# BuoyLoRaNode_Schematic.net
KiCad netlist of a schematic drawn in Altium Designer
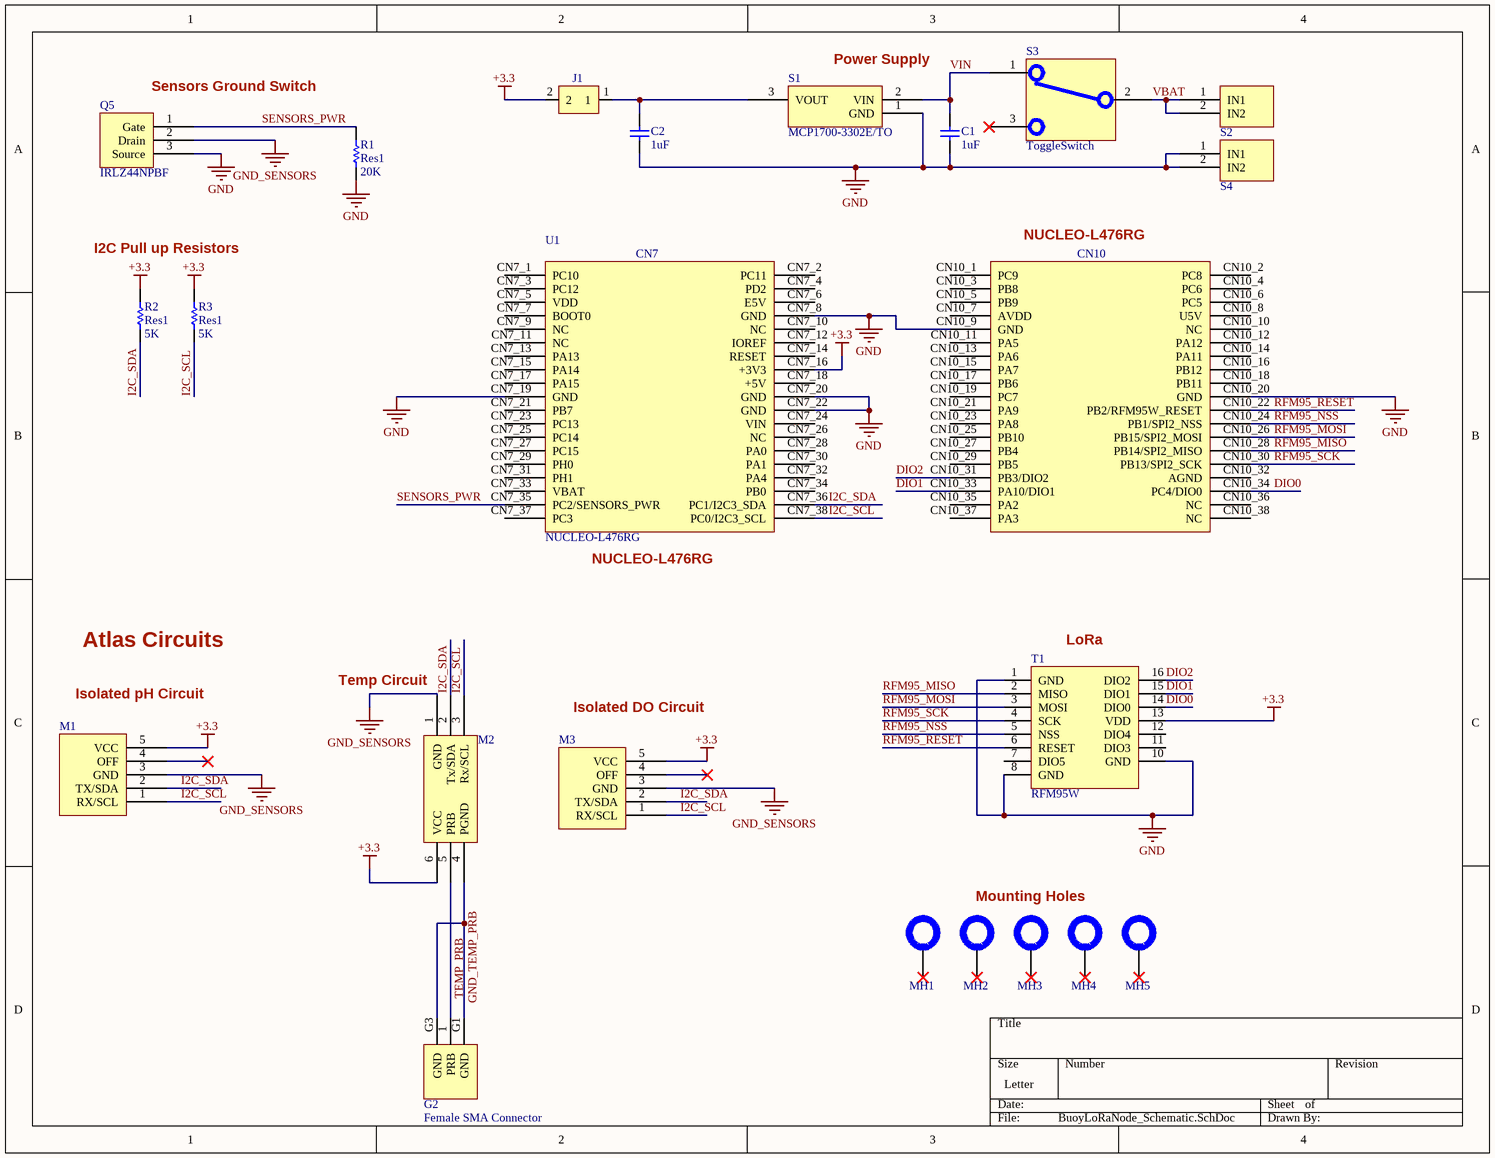
[diagram p0: BuoyLoRaNode_Schematic.SchDoc]

(export (version "E")
  (design (tool "Eeschema 10.0.6"))
  (components
    (comp (ref "C1")
      (value "1uF")
      (footprint "C1uFTantalum")
      (description "CAP TANT 1UF 10% 35V RADIAL")
      (fields
        (field (name "MANUFACTURER") "KEMET")
        (field (name "MANUFACTURER PART NUMBER") "T350A105K035AS7301")
      )
      (libsource (lib "BuoyLoRaNode") (part "T350A105K035AS7301"))
    )
    (comp (ref "C2")
      (value "1uF")
      (footprint "C1uFTantalum")
      (description "CAP TANT 1UF 10% 35V RADIAL")
      (fields
        (field (name "MANUFACTURER") "KEMET")
        (field (name "MANUFACTURER PART NUMBER") "T350A105K035AS7301")
      )
      (libsource (lib "BuoyLoRaNode") (part "T350A105K035AS7301"))
    )
    (comp (ref "G2")
      (value "Female SMA Connector")
      (footprint "SmaFemaleConnectorEdgeMount")
      (libsource (lib "BuoyLoRaNode") (part "Female SMA Connector"))
    )
    (comp (ref "J1")
      (value "2PinMaleJumper")
      (footprint "2MaleJumper")
      (libsource (lib "BuoyLoRaNode") (part "2PinMaleJumper"))
    )
    (comp (ref "M1")
      (value "Isolated pH Sensor")
      (footprint "ATLASISOLATEDPHSENSOR")
      (libsource (lib "BuoyLoRaNode") (part "Atlas Isolated pH Sensor"))
    )
    (comp (ref "M2")
      (value "EZO™ RTD Temperature Circuit")
      (footprint "AtlasTemperatureSensor")
      (libsource (lib "BuoyLoRaNode") (part "EZO™ RTD Temperature Circuit"))
    )
    (comp (ref "M3")
      (value "Isolated DO Sensor")
      (footprint "ATLASISOLATEDDOSENSOR")
      (libsource (lib "BuoyLoRaNode") (part "Atlas Isolated DO Sensor"))
    )
    (comp (ref "MH1")
      (value "MountingHole_3.4mmHole")
      (footprint "MountingHole")
      (libsource (lib "BuoyLoRaNode") (part "MountingHole"))
    )
    (comp (ref "MH2")
      (value "MountingHole_3.4mmHole")
      (footprint "MountingHole")
      (libsource (lib "BuoyLoRaNode") (part "MountingHole"))
    )
    (comp (ref "MH3")
      (value "MountingHole_3.4mmHole")
      (footprint "MountingHole")
      (libsource (lib "BuoyLoRaNode") (part "MountingHole"))
    )
    (comp (ref "MH4")
      (value "MountingHole_3.4mmHole")
      (footprint "MountingHole")
      (libsource (lib "BuoyLoRaNode") (part "MountingHole"))
    )
    (comp (ref "MH5")
      (value "MountingHole_3.4mmHole")
      (footprint "MountingHole")
      (libsource (lib "BuoyLoRaNode") (part "MountingHole"))
    )
    (comp (ref "Q5")
      (value "IRLZ44NPBF")
      (footprint "IRLZ44N")
      (description "INFINEON - IRLZ44NPBF - MOSFET, N, 55V, 41A, TO-220")
      (fields (field (name "MANUFACTURER") "International Rectifier"))
      (libsource (lib "BuoyLoRaNode") (part "IRLZ44NPBF"))
    )
    (comp (ref "R1")
      (value "Res1")
      (footprint "AXIAL-0.3")
      (description "Resistor")
      (fields (field (name "ALTIUM_VALUE") "20K") (field (name "PUBLISHER") "Altium Limited"))
      (libsource (lib "Miscellaneous Devices") (part "Res1"))
    )
    (comp (ref "R2")
      (value "Res1")
      (footprint "AXIAL-0.3")
      (description "Resistor")
      (fields (field (name "ALTIUM_VALUE") "5K") (field (name "PUBLISHER") "Altium Limited"))
      (libsource (lib "Miscellaneous Devices") (part "Res1"))
    )
    (comp (ref "R3")
      (value "Res1")
      (footprint "AXIAL-0.3")
      (description "Resistor")
      (fields (field (name "ALTIUM_VALUE") "5K") (field (name "PUBLISHER") "Altium Limited"))
      (libsource (lib "Miscellaneous Devices") (part "Res1"))
    )
    (comp (ref "S1")
      (value "MCP1700-3302E/TO")
      (footprint "MCP1700")
      (description "LDO Regulator Pos 3.3V 0.25A 3-Pin TO-92 Bag")
      (fields (field (name "MANUFACTURER") "Microchip"))
      (libsource (lib "GPSLoRaNode") (part "MCP1700-3302E/TO"))
    )
    (comp (ref "S2")
      (value "2PositionScrewTerminal")
      (footprint "2POSITIONSCREWTERMINAL")
      (fields
        (field (name "MANUFACTURER") "Phoenix Contact")
        (field (name "MANUFACTURER PART NUMBER") "1725656")
        (field (name "VOLTAGE") "125V")
      )
      (libsource (lib "BuoyLoRaNode") (part "2PositionScrewTerminal"))
    )
    (comp (ref "S3")
      (value "ToggleSwitch")
      (footprint "ToggleSwitch")
      (libsource (lib "BuoyLoRaNode") (part "ToggleSwitch"))
    )
    (comp (ref "S4")
      (value "2PositionScrewTerminal")
      (footprint "2POSITIONSCREWTERMINAL")
      (fields
        (field (name "MANUFACTURER") "Phoenix Contact")
        (field (name "MANUFACTURER PART NUMBER") "1725656")
        (field (name "VOLTAGE") "125V")
      )
      (libsource (lib "BuoyLoRaNode") (part "2PositionScrewTerminal"))
    )
    (comp (ref "T1")
      (value "RFM95W")
      (footprint "RFM95WBreakout")
      (description "RFM95W Breakout Board")
      (fields (field (name "MANUFACTURER") "Molex") (field (name "MANUFACTURER PART NUMBER") "22-10-2061"))
      (libsource (lib "BuoyLoRaNode") (part "RFM95W"))
    )
    (comp (ref "U1")
      (value "NUCLEO-L476RG")
      (footprint "NUCLEOL476RG")
      (description "16/32-BITS MICROS")
      (fields (field (name "MANUFACTURER") "STMicroelectronics"))
      (libsource (lib "BuoyLoRaNode") (part "NUCLEO-L476RG"))
    )
  )
  (nets
    (net (code "1") (name "+3.3") (class "Default")
      (node (ref "J1") (pin "2") (pinfunction "2_2") (pintype "passive"))
      (node (ref "M1") (pin "5") (pinfunction "VCC_5") (pintype "passive"))
      (node (ref "M2") (pin "6") (pinfunction "VCC_6") (pintype "passive"))
      (node (ref "M3") (pin "5") (pinfunction "VCC_5") (pintype "passive"))
      (node (ref "R2") (pin "2") (pinfunction "2_2") (pintype "passive"))
      (node (ref "R3") (pin "2") (pinfunction "2_2") (pintype "passive"))
      (node (ref "T1") (pin "13") (pinfunction "VDD_13") (pintype "passive"))
      (node (ref "U1") (pin "CN7_16") (pinfunction "+3V3_CN7_16") (pintype "passive"))
    )
    (net (code "2") (name "/DIO0") (class "Default")
      (node (ref "T1") (pin "14") (pinfunction "DIO0_14") (pintype "passive"))
      (node (ref "U1") (pin "CN10_34") (pinfunction "PC4/DIO0_CN10_34") (pintype "passive"))
    )
    (net (code "3") (name "/DIO1") (class "Default")
      (node (ref "T1") (pin "15") (pinfunction "DIO1_15") (pintype "passive"))
      (node (ref "U1") (pin "CN10_33") (pinfunction "PA10/DIO1_CN10_33") (pintype "passive"))
    )
    (net (code "4") (name "/DIO2") (class "Default")
      (node (ref "T1") (pin "16") (pinfunction "DIO2_16") (pintype "passive"))
      (node (ref "U1") (pin "CN10_31") (pinfunction "PB3/DIO2_CN10_31") (pintype "passive"))
    )
    (net (code "5") (name "/GND_TEMP_PRB") (class "Default")
      (node (ref "G2") (pin "G1") (pinfunction "GND_G1") (pintype "passive"))
      (node (ref "G2") (pin "G3") (pinfunction "GND_G3") (pintype "passive"))
      (node (ref "M2") (pin "4") (pinfunction "PGND_4") (pintype "passive"))
    )
    (net (code "6") (name "/I2C_SCL") (class "Default")
      (node (ref "M1") (pin "1") (pinfunction "RX/SCL_1") (pintype "passive"))
      (node (ref "M2") (pin "3") (pinfunction "Rx/SCL_3") (pintype "passive"))
      (node (ref "M3") (pin "1") (pinfunction "RX/SCL_1") (pintype "passive"))
      (node (ref "R3") (pin "1") (pinfunction "1_1") (pintype "passive"))
      (node (ref "U1") (pin "CN7_38") (pinfunction "PC0/I2C3_SCL_CN7_38") (pintype "passive"))
    )
    (net (code "7") (name "/I2C_SDA") (class "Default")
      (node (ref "M1") (pin "2") (pinfunction "TX/SDA_2") (pintype "passive"))
      (node (ref "M2") (pin "2") (pinfunction "Tx/SDA_2") (pintype "passive"))
      (node (ref "M3") (pin "2") (pinfunction "TX/SDA_2") (pintype "passive"))
      (node (ref "R2") (pin "1") (pinfunction "1_1") (pintype "passive"))
      (node (ref "U1") (pin "CN7_36") (pinfunction "PC1/I2C3_SDA_CN7_36") (pintype "passive"))
    )
    (net (code "8") (name "/RFM95_MISO") (class "Default")
      (node (ref "T1") (pin "2") (pinfunction "MISO_2") (pintype "passive"))
      (node (ref "U1") (pin "CN10_28") (pinfunction "PB14/SPI2_MISO_CN10_28") (pintype "passive"))
    )
    (net (code "9") (name "/RFM95_MOSI") (class "Default")
      (node (ref "T1") (pin "3") (pinfunction "MOSI_3") (pintype "passive"))
      (node (ref "U1") (pin "CN10_26") (pinfunction "PB15/SPI2_MOSI_CN10_26") (pintype "passive"))
    )
    (net (code "10") (name "/RFM95_NSS") (class "Default")
      (node (ref "T1") (pin "5") (pinfunction "NSS_5") (pintype "passive"))
      (node (ref "U1") (pin "CN10_24") (pinfunction "PB1/SPI2_NSS_CN10_24") (pintype "passive"))
    )
    (net (code "11") (name "/RFM95_RESET") (class "Default")
      (node (ref "T1") (pin "6") (pinfunction "RESET_6") (pintype "passive"))
      (node (ref "U1") (pin "CN10_22") (pinfunction "PB2/RFM95W_RESET_CN10_22") (pintype "passive"))
    )
    (net (code "12") (name "/RFM95_SCK") (class "Default")
      (node (ref "T1") (pin "4") (pinfunction "SCK_4") (pintype "passive"))
      (node (ref "U1") (pin "CN10_30") (pinfunction "PB13/SPI2_SCK_CN10_30") (pintype "passive"))
    )
    (net (code "13") (name "/SENSORS_PWR") (class "Default")
      (node (ref "Q5") (pin "1") (pinfunction "Gate_1") (pintype "passive"))
      (node (ref "R1") (pin "2") (pinfunction "2_2") (pintype "passive"))
      (node (ref "U1") (pin "CN7_35") (pinfunction "PC2/SENSORS_PWR_CN7_35") (pintype "passive"))
    )
    (net (code "14") (name "/TEMP_PRB") (class "Default")
      (node (ref "G2") (pin "1") (pinfunction "PRB_1") (pintype "passive"))
      (node (ref "M2") (pin "5") (pinfunction "PRB_5") (pintype "passive"))
    )
    (net (code "15") (name "/VBAT") (class "Default")
      (node (ref "S2") (pin "1") (pinfunction "IN1_1") (pintype "passive"))
      (node (ref "S2") (pin "2") (pinfunction "IN2_2") (pintype "passive"))
      (node (ref "S3") (pin "2") (pinfunction "COM_2") (pintype "passive"))
    )
    (net (code "16") (name "/VIN") (class "Default")
      (node (ref "C1") (pin "2") (pinfunction "2_2") (pintype "passive"))
      (node (ref "S1") (pin "2") (pinfunction "VIN_2") (pintype "passive"))
      (node (ref "S3") (pin "1") (pinfunction "L1_1") (pintype "passive"))
    )
    (net (code "17") (name "GND") (class "Default")
      (node (ref "C1") (pin "1") (pinfunction "1_1") (pintype "passive"))
      (node (ref "C2") (pin "1") (pinfunction "1_1") (pintype "passive"))
      (node (ref "Q5") (pin "3") (pinfunction "Source_3") (pintype "passive"))
      (node (ref "R1") (pin "1") (pinfunction "1_1") (pintype "passive"))
      (node (ref "S1") (pin "1") (pinfunction "GND_1") (pintype "passive"))
      (node (ref "S4") (pin "1") (pinfunction "IN1_1") (pintype "passive"))
      (node (ref "S4") (pin "2") (pinfunction "IN2_2") (pintype "passive"))
      (node (ref "T1") (pin "1") (pinfunction "GND_1") (pintype "passive"))
      (node (ref "T1") (pin "10") (pinfunction "GND_10") (pintype "passive"))
      (node (ref "T1") (pin "8") (pinfunction "GND_8") (pintype "passive"))
      (node (ref "U1") (pin "CN10_20") (pinfunction "GND_CN10_20") (pintype "passive"))
      (node (ref "U1") (pin "CN10_9") (pinfunction "GND_CN10_9") (pintype "passive"))
      (node (ref "U1") (pin "CN7_19") (pinfunction "GND_CN7_19") (pintype "passive"))
      (node (ref "U1") (pin "CN7_20") (pinfunction "GND_CN7_20") (pintype "passive"))
      (node (ref "U1") (pin "CN7_22") (pinfunction "GND_CN7_22") (pintype "passive"))
      (node (ref "U1") (pin "CN7_8") (pinfunction "GND_CN7_8") (pintype "passive"))
    )
    (net (code "18") (name "GND_SENSORS") (class "Default")
      (node (ref "M1") (pin "3") (pinfunction "GND_3") (pintype "passive"))
      (node (ref "M2") (pin "1") (pinfunction "GND_1") (pintype "passive"))
      (node (ref "M3") (pin "3") (pinfunction "GND_3") (pintype "passive"))
      (node (ref "Q5") (pin "2") (pinfunction "Drain_2") (pintype "passive"))
    )
    (net (code "19") (name "Net-(S1-VOUT)") (class "Default")
      (node (ref "C2") (pin "2") (pinfunction "2_2") (pintype "passive"))
      (node (ref "J1") (pin "1") (pinfunction "1_1") (pintype "passive"))
      (node (ref "S1") (pin "3") (pinfunction "VOUT_3") (pintype "passive"))
    )
    (net (code "20") (name "unconnected-(M1-OFF-Pad4)") (class "Default")
      (node (ref "M1") (pin "4") (pinfunction "OFF_4") (pintype "passive+no_connect"))
    )
    (net (code "21") (name "unconnected-(M3-OFF-Pad4)") (class "Default")
      (node (ref "M3") (pin "4") (pinfunction "OFF_4") (pintype "passive+no_connect"))
    )
    (net (code "22") (name "unconnected-(MH1-Pad1)") (class "Default")
      (node (ref "MH1") (pin "1") (pinfunction "1_1") (pintype "passive+no_connect"))
    )
    (net (code "23") (name "unconnected-(MH2-Pad1)") (class "Default")
      (node (ref "MH2") (pin "1") (pinfunction "1_1") (pintype "passive+no_connect"))
    )
    (net (code "24") (name "unconnected-(MH3-Pad1)") (class "Default")
      (node (ref "MH3") (pin "1") (pinfunction "1_1") (pintype "passive+no_connect"))
    )
    (net (code "25") (name "unconnected-(MH4-Pad1)") (class "Default")
      (node (ref "MH4") (pin "1") (pinfunction "1_1") (pintype "passive+no_connect"))
    )
    (net (code "26") (name "unconnected-(MH5-Pad1)") (class "Default")
      (node (ref "MH5") (pin "1") (pinfunction "1_1") (pintype "passive+no_connect"))
    )
    (net (code "27") (name "unconnected-(S3-L2-Pad3)") (class "Default")
      (node (ref "S3") (pin "3") (pinfunction "L2_3") (pintype "passive+no_connect"))
    )
    (net (code "28") (name "unconnected-(T1-DIO3-Pad11)") (class "Default")
      (node (ref "T1") (pin "11") (pinfunction "DIO3_11") (pintype "passive"))
    )
    (net (code "29") (name "unconnected-(T1-DIO4-Pad12)") (class "Default")
      (node (ref "T1") (pin "12") (pinfunction "DIO4_12") (pintype "passive"))
    )
    (net (code "30") (name "unconnected-(T1-DIO5-Pad7)") (class "Default")
      (node (ref "T1") (pin "7") (pinfunction "DIO5_7") (pintype "passive"))
    )
    (net (code "31") (name "unconnected-(U1-+5V-PadCN7_18)") (class "Default")
      (node (ref "U1") (pin "CN7_18") (pinfunction "+5V_CN7_18") (pintype "passive"))
    )
    (net (code "32") (name "unconnected-(U1-AGND-PadCN10_32)") (class "Default")
      (node (ref "U1") (pin "CN10_32") (pinfunction "AGND_CN10_32") (pintype "passive"))
    )
    (net (code "33") (name "unconnected-(U1-AVDD-PadCN10_7)") (class "Default")
      (node (ref "U1") (pin "CN10_7") (pinfunction "AVDD_CN10_7") (pintype "passive"))
    )
    (net (code "34") (name "unconnected-(U1-BOOT0-PadCN7_7)") (class "Default")
      (node (ref "U1") (pin "CN7_7") (pinfunction "BOOT0_CN7_7") (pintype "passive"))
    )
    (net (code "35") (name "unconnected-(U1-E5V-PadCN7_6)") (class "Default")
      (node (ref "U1") (pin "CN7_6") (pinfunction "E5V_CN7_6") (pintype "passive"))
    )
    (net (code "36") (name "unconnected-(U1-IOREF-PadCN7_12)") (class "Default")
      (node (ref "U1") (pin "CN7_12") (pinfunction "IOREF_CN7_12") (pintype "passive"))
    )
    (net (code "37") (name "unconnected-(U1-NC-PadCN7_9)") (class "Default")
      (node (ref "U1") (pin "CN7_9") (pinfunction "NC_CN7_9") (pintype "passive"))
    )
    (net (code "38") (name "unconnected-(U1-NC-PadCN7_10)") (class "Default")
      (node (ref "U1") (pin "CN7_10") (pinfunction "NC_CN7_10") (pintype "passive"))
    )
    (net (code "39") (name "unconnected-(U1-NC-PadCN7_11)") (class "Default")
      (node (ref "U1") (pin "CN7_11") (pinfunction "NC_CN7_11") (pintype "passive"))
    )
    (net (code "40") (name "unconnected-(U1-NC-PadCN7_26)") (class "Default")
      (node (ref "U1") (pin "CN7_26") (pinfunction "NC_CN7_26") (pintype "passive"))
    )
    (net (code "41") (name "unconnected-(U1-NC-PadCN10_10)") (class "Default")
      (node (ref "U1") (pin "CN10_10") (pinfunction "NC_CN10_10") (pintype "passive"))
    )
    (net (code "42") (name "unconnected-(U1-NC-PadCN10_36)") (class "Default")
      (node (ref "U1") (pin "CN10_36") (pinfunction "NC_CN10_36") (pintype "passive"))
    )
    (net (code "43") (name "unconnected-(U1-NC-PadCN10_38)") (class "Default")
      (node (ref "U1") (pin "CN10_38") (pinfunction "NC_CN10_38") (pintype "passive"))
    )
    (net (code "44") (name "unconnected-(U1-PA0-PadCN7_28)") (class "Default")
      (node (ref "U1") (pin "CN7_28") (pinfunction "PA0_CN7_28") (pintype "passive"))
    )
    (net (code "45") (name "unconnected-(U1-PA1-PadCN7_30)") (class "Default")
      (node (ref "U1") (pin "CN7_30") (pinfunction "PA1_CN7_30") (pintype "passive"))
    )
    (net (code "46") (name "unconnected-(U1-PA2-PadCN10_35)") (class "Default")
      (node (ref "U1") (pin "CN10_35") (pinfunction "PA2_CN10_35") (pintype "passive"))
    )
    (net (code "47") (name "unconnected-(U1-PA3-PadCN10_37)") (class "Default")
      (node (ref "U1") (pin "CN10_37") (pinfunction "PA3_CN10_37") (pintype "passive"))
    )
    (net (code "48") (name "unconnected-(U1-PA4-PadCN7_32)") (class "Default")
      (node (ref "U1") (pin "CN7_32") (pinfunction "PA4_CN7_32") (pintype "passive"))
    )
    (net (code "49") (name "unconnected-(U1-PA5-PadCN10_11)") (class "Default")
      (node (ref "U1") (pin "CN10_11") (pinfunction "PA5_CN10_11") (pintype "passive"))
    )
    (net (code "50") (name "unconnected-(U1-PA6-PadCN10_13)") (class "Default")
      (node (ref "U1") (pin "CN10_13") (pinfunction "PA6_CN10_13") (pintype "passive"))
    )
    (net (code "51") (name "unconnected-(U1-PA7-PadCN10_15)") (class "Default")
      (node (ref "U1") (pin "CN10_15") (pinfunction "PA7_CN10_15") (pintype "passive"))
    )
    (net (code "52") (name "unconnected-(U1-PA8-PadCN10_23)") (class "Default")
      (node (ref "U1") (pin "CN10_23") (pinfunction "PA8_CN10_23") (pintype "passive"))
    )
    (net (code "53") (name "unconnected-(U1-PA9-PadCN10_21)") (class "Default")
      (node (ref "U1") (pin "CN10_21") (pinfunction "PA9_CN10_21") (pintype "passive"))
    )
    (net (code "54") (name "unconnected-(U1-PA11-PadCN10_14)") (class "Default")
      (node (ref "U1") (pin "CN10_14") (pinfunction "PA11_CN10_14") (pintype "passive"))
    )
    (net (code "55") (name "unconnected-(U1-PA12-PadCN10_12)") (class "Default")
      (node (ref "U1") (pin "CN10_12") (pinfunction "PA12_CN10_12") (pintype "passive"))
    )
    (net (code "56") (name "unconnected-(U1-PA13-PadCN7_13)") (class "Default")
      (node (ref "U1") (pin "CN7_13") (pinfunction "PA13_CN7_13") (pintype "passive"))
    )
    (net (code "57") (name "unconnected-(U1-PA14-PadCN7_15)") (class "Default")
      (node (ref "U1") (pin "CN7_15") (pinfunction "PA14_CN7_15") (pintype "passive"))
    )
    (net (code "58") (name "unconnected-(U1-PA15-PadCN7_17)") (class "Default")
      (node (ref "U1") (pin "CN7_17") (pinfunction "PA15_CN7_17") (pintype "passive"))
    )
    (net (code "59") (name "unconnected-(U1-PB0-PadCN7_34)") (class "Default")
      (node (ref "U1") (pin "CN7_34") (pinfunction "PB0_CN7_34") (pintype "passive"))
    )
    (net (code "60") (name "unconnected-(U1-PB4-PadCN10_27)") (class "Default")
      (node (ref "U1") (pin "CN10_27") (pinfunction "PB4_CN10_27") (pintype "passive"))
    )
    (net (code "61") (name "unconnected-(U1-PB5-PadCN10_29)") (class "Default")
      (node (ref "U1") (pin "CN10_29") (pinfunction "PB5_CN10_29") (pintype "passive"))
    )
    (net (code "62") (name "unconnected-(U1-PB6-PadCN10_17)") (class "Default")
      (node (ref "U1") (pin "CN10_17") (pinfunction "PB6_CN10_17") (pintype "passive"))
    )
    (net (code "63") (name "unconnected-(U1-PB7-PadCN7_21)") (class "Default")
      (node (ref "U1") (pin "CN7_21") (pinfunction "PB7_CN7_21") (pintype "passive"))
    )
    (net (code "64") (name "unconnected-(U1-PB8-PadCN10_3)") (class "Default")
      (node (ref "U1") (pin "CN10_3") (pinfunction "PB8_CN10_3") (pintype "passive"))
    )
    (net (code "65") (name "unconnected-(U1-PB9-PadCN10_5)") (class "Default")
      (node (ref "U1") (pin "CN10_5") (pinfunction "PB9_CN10_5") (pintype "passive"))
    )
    (net (code "66") (name "unconnected-(U1-PB10-PadCN10_25)") (class "Default")
      (node (ref "U1") (pin "CN10_25") (pinfunction "PB10_CN10_25") (pintype "passive"))
    )
    (net (code "67") (name "unconnected-(U1-PB11-PadCN10_18)") (class "Default")
      (node (ref "U1") (pin "CN10_18") (pinfunction "PB11_CN10_18") (pintype "passive"))
    )
    (net (code "68") (name "unconnected-(U1-PB12-PadCN10_16)") (class "Default")
      (node (ref "U1") (pin "CN10_16") (pinfunction "PB12_CN10_16") (pintype "passive"))
    )
    (net (code "69") (name "unconnected-(U1-PC3-PadCN7_37)") (class "Default")
      (node (ref "U1") (pin "CN7_37") (pinfunction "PC3_CN7_37") (pintype "passive"))
    )
    (net (code "70") (name "unconnected-(U1-PC5-PadCN10_6)") (class "Default")
      (node (ref "U1") (pin "CN10_6") (pinfunction "PC5_CN10_6") (pintype "passive"))
    )
    (net (code "71") (name "unconnected-(U1-PC6-PadCN10_4)") (class "Default")
      (node (ref "U1") (pin "CN10_4") (pinfunction "PC6_CN10_4") (pintype "passive"))
    )
    (net (code "72") (name "unconnected-(U1-PC7-PadCN10_19)") (class "Default")
      (node (ref "U1") (pin "CN10_19") (pinfunction "PC7_CN10_19") (pintype "passive"))
    )
    (net (code "73") (name "unconnected-(U1-PC8-PadCN10_2)") (class "Default")
      (node (ref "U1") (pin "CN10_2") (pinfunction "PC8_CN10_2") (pintype "passive"))
    )
    (net (code "74") (name "unconnected-(U1-PC9-PadCN10_1)") (class "Default")
      (node (ref "U1") (pin "CN10_1") (pinfunction "PC9_CN10_1") (pintype "passive"))
    )
    (net (code "75") (name "unconnected-(U1-PC10-PadCN7_1)") (class "Default")
      (node (ref "U1") (pin "CN7_1") (pinfunction "PC10_CN7_1") (pintype "passive"))
    )
    (net (code "76") (name "unconnected-(U1-PC11-PadCN7_2)") (class "Default")
      (node (ref "U1") (pin "CN7_2") (pinfunction "PC11_CN7_2") (pintype "passive"))
    )
    (net (code "77") (name "unconnected-(U1-PC12-PadCN7_3)") (class "Default")
      (node (ref "U1") (pin "CN7_3") (pinfunction "PC12_CN7_3") (pintype "passive"))
    )
    (net (code "78") (name "unconnected-(U1-PC13-PadCN7_23)") (class "Default")
      (node (ref "U1") (pin "CN7_23") (pinfunction "PC13_CN7_23") (pintype "passive"))
    )
    (net (code "79") (name "unconnected-(U1-PC14-PadCN7_25)") (class "Default")
      (node (ref "U1") (pin "CN7_25") (pinfunction "PC14_CN7_25") (pintype "passive"))
    )
    (net (code "80") (name "unconnected-(U1-PC15-PadCN7_27)") (class "Default")
      (node (ref "U1") (pin "CN7_27") (pinfunction "PC15_CN7_27") (pintype "passive"))
    )
    (net (code "81") (name "unconnected-(U1-PD2-PadCN7_4)") (class "Default")
      (node (ref "U1") (pin "CN7_4") (pinfunction "PD2_CN7_4") (pintype "passive"))
    )
    (net (code "82") (name "unconnected-(U1-PH0-PadCN7_29)") (class "Default")
      (node (ref "U1") (pin "CN7_29") (pinfunction "PH0_CN7_29") (pintype "passive"))
    )
    (net (code "83") (name "unconnected-(U1-PH1-PadCN7_31)") (class "Default")
      (node (ref "U1") (pin "CN7_31") (pinfunction "PH1_CN7_31") (pintype "passive"))
    )
    (net (code "84") (name "unconnected-(U1-RESET-PadCN7_14)") (class "Default")
      (node (ref "U1") (pin "CN7_14") (pinfunction "RESET_CN7_14") (pintype "passive"))
    )
    (net (code "85") (name "unconnected-(U1-U5V-PadCN10_8)") (class "Default")
      (node (ref "U1") (pin "CN10_8") (pinfunction "U5V_CN10_8") (pintype "passive"))
    )
    (net (code "86") (name "unconnected-(U1-VBAT-PadCN7_33)") (class "Default")
      (node (ref "U1") (pin "CN7_33") (pinfunction "VBAT_CN7_33") (pintype "passive"))
    )
    (net (code "87") (name "unconnected-(U1-VDD-PadCN7_5)") (class "Default")
      (node (ref "U1") (pin "CN7_5") (pinfunction "VDD_CN7_5") (pintype "passive"))
    )
    (net (code "88") (name "unconnected-(U1-VIN-PadCN7_24)") (class "Default")
      (node (ref "U1") (pin "CN7_24") (pinfunction "VIN_CN7_24") (pintype "passive"))
    )
  )
)
